# ESP32_mini.net
KiCad netlist of a schematic drawn in EAGLE
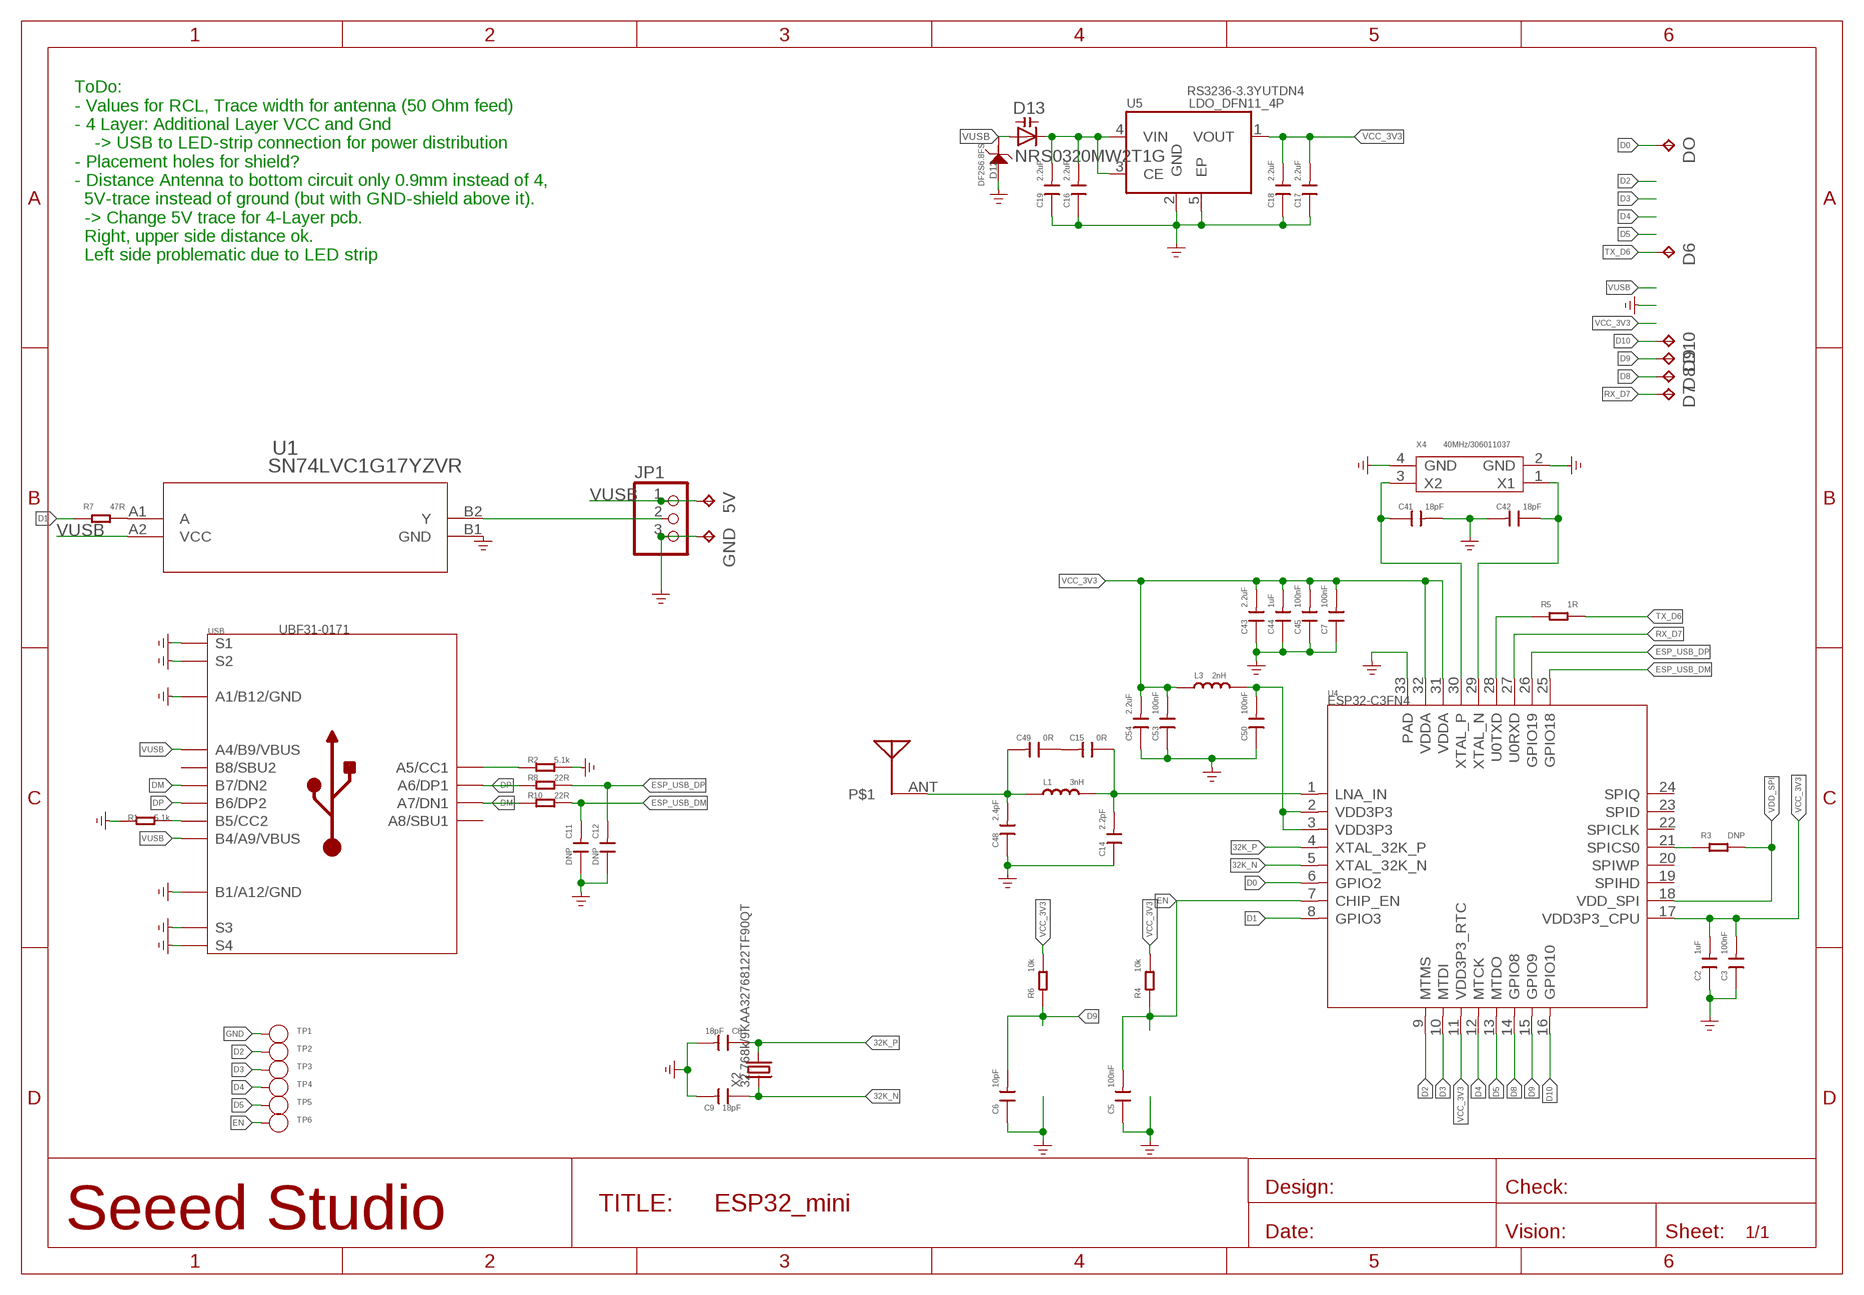
[diagram p0: schematic, sheet 1]

(export (version "E")
  (design (tool "Eeschema 10.0.6"))
  (components
    (comp (ref "5V")
      (value "TPTP07R")
      (footprint "eagle-import:TP07R")
      (libsource (lib "eagle-import") (part "TPTP07R"))
    )
    (comp (ref "C2")
      (value "1uF")
      (footprint "eagle-import:C0201")
      (libsource (lib "eagle-import") (part "CAP-0201"))
    )
    (comp (ref "C3")
      (value "100nF")
      (footprint "eagle-import:C0201")
      (libsource (lib "eagle-import") (part "CAP-0201"))
    )
    (comp (ref "C5")
      (value "100nF")
      (footprint "eagle-import:C0201")
      (libsource (lib "eagle-import") (part "CAP-0201"))
    )
    (comp (ref "C6")
      (value "10pF")
      (footprint "eagle-import:C0201")
      (libsource (lib "eagle-import") (part "CAP-0201"))
    )
    (comp (ref "C7")
      (value "100nF")
      (footprint "eagle-import:C0201")
      (libsource (lib "eagle-import") (part "CAP-0201"))
    )
    (comp (ref "C8")
      (value "18pF")
      (footprint "eagle-import:C0201")
      (libsource (lib "eagle-import") (part "CAP-0201"))
    )
    (comp (ref "C9")
      (value "18pF")
      (footprint "eagle-import:C0201")
      (libsource (lib "eagle-import") (part "CAP-0201"))
    )
    (comp (ref "C11")
      (value "DNP")
      (footprint "eagle-import:C0201")
      (libsource (lib "eagle-import") (part "CAP-0201"))
    )
    (comp (ref "C12")
      (value "DNP")
      (footprint "eagle-import:C0201")
      (libsource (lib "eagle-import") (part "CAP-0201"))
    )
    (comp (ref "C14")
      (value "2.2pF")
      (footprint "eagle-import:C0201")
      (libsource (lib "eagle-import") (part "CAP-0201"))
    )
    (comp (ref "C15")
      (value "0R")
      (footprint "eagle-import:C0201")
      (libsource (lib "eagle-import") (part "CAP-0201"))
    )
    (comp (ref "C16")
      (value "2.2uF")
      (footprint "eagle-import:C0201")
      (libsource (lib "eagle-import") (part "CAP-0201"))
    )
    (comp (ref "C17")
      (value "2.2uF")
      (footprint "eagle-import:C0201")
      (libsource (lib "eagle-import") (part "CAP-0201"))
    )
    (comp (ref "C18")
      (value "2.2uF")
      (footprint "eagle-import:C0201")
      (libsource (lib "eagle-import") (part "CAP-0201"))
    )
    (comp (ref "C19")
      (value "2.2uF")
      (footprint "eagle-import:C0201")
      (libsource (lib "eagle-import") (part "CAP-0201"))
    )
    (comp (ref "C41")
      (value "18pF")
      (footprint "eagle-import:C0201")
      (libsource (lib "eagle-import") (part "CAP-0201"))
    )
    (comp (ref "C42")
      (value "18pF")
      (footprint "eagle-import:C0201")
      (libsource (lib "eagle-import") (part "CAP-0201"))
    )
    (comp (ref "C43")
      (value "2.2uF")
      (footprint "eagle-import:C0201")
      (libsource (lib "eagle-import") (part "CAP-0201"))
    )
    (comp (ref "C44")
      (value "1uF")
      (footprint "eagle-import:C0201")
      (libsource (lib "eagle-import") (part "CAP-0201"))
    )
    (comp (ref "C45")
      (value "100nF")
      (footprint "eagle-import:C0201")
      (libsource (lib "eagle-import") (part "CAP-0201"))
    )
    (comp (ref "C48")
      (value "2.4pF")
      (footprint "eagle-import:C0201")
      (libsource (lib "eagle-import") (part "CAP-0201"))
    )
    (comp (ref "C49")
      (value "0R")
      (footprint "eagle-import:C0201")
      (libsource (lib "eagle-import") (part "CAP-0201"))
    )
    (comp (ref "C50")
      (value "100nF")
      (footprint "eagle-import:C0201")
      (libsource (lib "eagle-import") (part "CAP-0201"))
    )
    (comp (ref "C53")
      (value "100nF")
      (footprint "eagle-import:C0201")
      (libsource (lib "eagle-import") (part "CAP-0201"))
    )
    (comp (ref "C54")
      (value "2.2uF")
      (footprint "eagle-import:C0201")
      (libsource (lib "eagle-import") (part "CAP-0201"))
    )
    (comp (ref "D6")
      (value "TPTP07R")
      (footprint "eagle-import:TP07R")
      (libsource (lib "eagle-import") (part "TPTP07R"))
    )
    (comp (ref "D7")
      (value "TPTP07R")
      (footprint "eagle-import:TP07R")
      (libsource (lib "eagle-import") (part "TPTP07R"))
    )
    (comp (ref "D8")
      (value "TPTP07R")
      (footprint "eagle-import:TP07R")
      (libsource (lib "eagle-import") (part "TPTP07R"))
    )
    (comp (ref "D9")
      (value "TPTP07R")
      (footprint "eagle-import:TP07R")
      (libsource (lib "eagle-import") (part "TPTP07R"))
    )
    (comp (ref "D10")
      (value "TPTP07R")
      (footprint "eagle-import:TP07R")
      (libsource (lib "eagle-import") (part "TPTP07R"))
    )
    (comp (ref "D12")
      (value "DF2S6.8FS")
      (footprint "eagle-import:SOD-923")
      (libsource (lib "eagle-import") (part "D-ESD-2P'DF2S6.8FS'"))
    )
    (comp (ref "D13")
      (value "NRS0320MW2T1G")
      (footprint "eagle-import:SOD523")
      (libsource (lib "eagle-import") (part "DIODE_CAPACITANCE-SOD523"))
    )
    (comp (ref "DO")
      (value "TPTP09R")
      (footprint "eagle-import:TP09R")
      (libsource (lib "eagle-import") (part "TPTP09R"))
    )
    (comp (ref "GND")
      (value "TPTP07R")
      (footprint "eagle-import:TP07R")
      (libsource (lib "eagle-import") (part "TPTP07R"))
    )
    (comp (ref "JP1")
      (value "PINHD-1X3")
      (footprint "eagle-import:1X03")
      (libsource (lib "eagle-import") (part "PINHD-1X3"))
    )
    (comp (ref "L1")
      (value "3nH")
      (footprint "eagle-import:L0201")
      (libsource (lib "eagle-import") (part "INDUCTOR-0201"))
    )
    (comp (ref "L3")
      (value "2nH")
      (footprint "eagle-import:L0201")
      (libsource (lib "eagle-import") (part "INDUCTOR-0201"))
    )
    (comp (ref "R1")
      (value "5.1k")
      (footprint "eagle-import:R0201")
      (libsource (lib "eagle-import") (part "RES-0201"))
    )
    (comp (ref "R2")
      (value "5.1k")
      (footprint "eagle-import:R0201")
      (libsource (lib "eagle-import") (part "RES-0201"))
    )
    (comp (ref "R3")
      (value "DNP")
      (footprint "eagle-import:R0201")
      (libsource (lib "eagle-import") (part "RES-0201"))
    )
    (comp (ref "R4")
      (value "10k")
      (footprint "eagle-import:R0201")
      (libsource (lib "eagle-import") (part "RES-0201"))
    )
    (comp (ref "R5")
      (value "1R")
      (footprint "eagle-import:R0201")
      (libsource (lib "eagle-import") (part "RES-0201"))
    )
    (comp (ref "R6")
      (value "10k")
      (footprint "eagle-import:R0201")
      (libsource (lib "eagle-import") (part "RES-0201"))
    )
    (comp (ref "R7")
      (value "47R")
      (footprint "eagle-import:R0201")
      (libsource (lib "eagle-import") (part "RES-0201"))
    )
    (comp (ref "R8")
      (value "22R")
      (footprint "eagle-import:R0201")
      (libsource (lib "eagle-import") (part "RES-0201"))
    )
    (comp (ref "R10")
      (value "22R")
      (footprint "eagle-import:R0201")
      (libsource (lib "eagle-import") (part "RES-0201"))
    )
    (comp (ref "TP1")
      (value "DNP")
      (footprint "eagle-import:TP_3535")
      (libsource (lib "eagle-import") (part "TEST-POINT-35"))
    )
    (comp (ref "TP2")
      (value "DNP")
      (footprint "eagle-import:TP_3535")
      (libsource (lib "eagle-import") (part "TEST-POINT-35"))
    )
    (comp (ref "TP3")
      (value "DNP")
      (footprint "eagle-import:TP_3535")
      (libsource (lib "eagle-import") (part "TEST-POINT-35"))
    )
    (comp (ref "TP4")
      (value "DNP")
      (footprint "eagle-import:TP_3535")
      (libsource (lib "eagle-import") (part "TEST-POINT-35"))
    )
    (comp (ref "TP5")
      (value "DNP")
      (footprint "eagle-import:TP_3535")
      (libsource (lib "eagle-import") (part "TEST-POINT-35"))
    )
    (comp (ref "TP6")
      (value "DNP")
      (footprint "eagle-import:TP_3535")
      (libsource (lib "eagle-import") (part "TEST-POINT-35"))
    )
    (comp (ref "U$1")
      (value "KH5220-A36KH5220-A36")
      (footprint "eagle-import:KH5220-A36")
      (libsource (lib "eagle-import") (part "KH5220-A36KH5220-A36"))
    )
    (comp (ref "U1")
      (value "SN74LVC1G17YZVR")
      (footprint "eagle-import:YZV4")
      (fields (field (name "COPYRIGHT") "Copyright (C) 2024 Ultra Librarian. All rights reserved."))
      (libsource (lib "eagle-import") (part "SN74LVC1G17YZVR"))
    )
    (comp (ref "U4")
      (value "ESP32-C3FN4")
      (footprint "eagle-import:QFN32G-0.5-5X5MM")
      (libsource (lib "eagle-import") (part "MCU-ESP32-C3"))
    )
    (comp (ref "U5")
      (value "LDO_DFN11_4P")
      (footprint "eagle-import:LDO_DFN1_1_4P")
      (libsource (lib "eagle-import") (part "LDO_DFN11_4P"))
    )
    (comp (ref "USB")
      (value "UBF31-0171")
      (footprint "eagle-import:USB2.0-TYPE-C")
      (libsource (lib "eagle-import") (part "USB2.0-TYPE-C"))
    )
    (comp (ref "X2")
      (value "32.768k/9KAA32768122TF90QT")
      (footprint "eagle-import:X2-SMD-1.6X1.0X0.5MM")
      (libsource (lib "eagle-import") (part "CRYSTAL-2P-1610"))
    )
    (comp (ref "X4")
      (value "40MHz/306011037")
      (footprint "eagle-import:X4-SMD-2.0X1.6X0.5MM")
      (libsource (lib "eagle-import") (part "CRYSTAL-4P-2016"))
    )
  )
  (nets
    (net (code "1") (name "32K_N") (class "Default")
      (node (ref "C9") (pin "1") (pinfunction "1_1") (pintype "passive"))
      (node (ref "U4") (pin "5") (pinfunction "XTAL_32K_N_5") (pintype "bidirectional"))
      (node (ref "X2") (pin "1") (pinfunction "1_1") (pintype "passive"))
    )
    (net (code "2") (name "32K_P") (class "Default")
      (node (ref "C8") (pin "1") (pinfunction "1_1") (pintype "passive"))
      (node (ref "U4") (pin "4") (pinfunction "XTAL_32K_P_4") (pintype "bidirectional"))
      (node (ref "X2") (pin "2") (pinfunction "2_2") (pintype "passive"))
    )
    (net (code "3") (name "D0") (class "Default")
      (node (ref "DO") (pin "TP") (pinfunction "TP_TP") (pintype "input"))
      (node (ref "U4") (pin "6") (pinfunction "GPIO2_6") (pintype "bidirectional"))
    )
    (net (code "4") (name "D1") (class "Default")
      (node (ref "R7") (pin "2") (pinfunction "2_2") (pintype "passive"))
      (node (ref "U4") (pin "8") (pinfunction "GPIO3_8") (pintype "bidirectional"))
    )
    (net (code "5") (name "D2") (class "Default")
      (node (ref "TP2") (pin "T") (pinfunction "T_T") (pintype "bidirectional"))
      (node (ref "U4") (pin "9") (pinfunction "MTMS_9") (pintype "bidirectional"))
    )
    (net (code "6") (name "D3") (class "Default")
      (node (ref "TP3") (pin "T") (pinfunction "T_T") (pintype "bidirectional"))
      (node (ref "U4") (pin "10") (pinfunction "MTDI_10") (pintype "bidirectional"))
    )
    (net (code "7") (name "D4") (class "Default")
      (node (ref "TP4") (pin "T") (pinfunction "T_T") (pintype "bidirectional"))
      (node (ref "U4") (pin "12") (pinfunction "MTCK_12") (pintype "bidirectional"))
    )
    (net (code "8") (name "D5") (class "Default")
      (node (ref "TP5") (pin "T") (pinfunction "T_T") (pintype "bidirectional"))
      (node (ref "U4") (pin "13") (pinfunction "MTDO_13") (pintype "bidirectional"))
    )
    (net (code "9") (name "D8") (class "Default")
      (node (ref "D8") (pin "TP") (pinfunction "TP_TP") (pintype "input"))
      (node (ref "U4") (pin "14") (pinfunction "GPIO8_14") (pintype "bidirectional"))
    )
    (net (code "10") (name "D9") (class "Default")
      (node (ref "C6") (pin "2") (pinfunction "2_2") (pintype "passive"))
      (node (ref "D9") (pin "TP") (pinfunction "TP_TP") (pintype "input"))
      (node (ref "R6") (pin "1") (pinfunction "1_1") (pintype "passive"))
      (node (ref "U4") (pin "15") (pinfunction "GPIO9_15") (pintype "bidirectional"))
    )
    (net (code "11") (name "D10") (class "Default")
      (node (ref "D10") (pin "TP") (pinfunction "TP_TP") (pintype "input"))
      (node (ref "U4") (pin "16") (pinfunction "GPIO10_16") (pintype "bidirectional"))
    )
    (net (code "12") (name "DM") (class "Default")
      (node (ref "R10") (pin "1") (pinfunction "1_1") (pintype "passive"))
      (node (ref "USB") (pin "A7") (pinfunction "A7/DN1_A7") (pintype "bidirectional"))
      (node (ref "USB") (pin "B7") (pinfunction "B7/DN2_B7") (pintype "bidirectional"))
    )
    (net (code "13") (name "DP") (class "Default")
      (node (ref "R8") (pin "1") (pinfunction "1_1") (pintype "passive"))
      (node (ref "USB") (pin "A6") (pinfunction "A6/DP1_A6") (pintype "bidirectional"))
      (node (ref "USB") (pin "B6") (pinfunction "B6/DP2_B6") (pintype "bidirectional"))
    )
    (net (code "14") (name "EN") (class "Default")
      (node (ref "C5") (pin "2") (pinfunction "2_2") (pintype "passive"))
      (node (ref "R4") (pin "1") (pinfunction "1_1") (pintype "passive"))
      (node (ref "TP6") (pin "T") (pinfunction "T_T") (pintype "bidirectional"))
      (node (ref "U4") (pin "7") (pinfunction "CHIP_EN_7") (pintype "bidirectional"))
    )
    (net (code "15") (name "ESP_USB_DM") (class "Default")
      (node (ref "C11") (pin "2") (pinfunction "2_2") (pintype "passive"))
      (node (ref "R10") (pin "2") (pinfunction "2_2") (pintype "passive"))
      (node (ref "U4") (pin "25") (pinfunction "GPIO18_25") (pintype "bidirectional"))
    )
    (net (code "16") (name "ESP_USB_DP") (class "Default")
      (node (ref "C12") (pin "2") (pinfunction "2_2") (pintype "passive"))
      (node (ref "R8") (pin "2") (pinfunction "2_2") (pintype "passive"))
      (node (ref "U4") (pin "26") (pinfunction "GPIO19_26") (pintype "bidirectional"))
    )
    (net (code "17") (name "GND") (class "Default")
      (node (ref "C11") (pin "1") (pinfunction "1_1") (pintype "passive"))
      (node (ref "C12") (pin "1") (pinfunction "1_1") (pintype "passive"))
      (node (ref "C14") (pin "1") (pinfunction "1_1") (pintype "passive"))
      (node (ref "C16") (pin "1") (pinfunction "1_1") (pintype "passive"))
      (node (ref "C17") (pin "1") (pinfunction "1_1") (pintype "passive"))
      (node (ref "C18") (pin "1") (pinfunction "1_1") (pintype "passive"))
      (node (ref "C19") (pin "1") (pinfunction "1_1") (pintype "passive"))
      (node (ref "C2") (pin "1") (pinfunction "1_1") (pintype "passive"))
      (node (ref "C3") (pin "1") (pinfunction "1_1") (pintype "passive"))
      (node (ref "C41") (pin "2") (pinfunction "2_2") (pintype "passive"))
      (node (ref "C42") (pin "2") (pinfunction "2_2") (pintype "passive"))
      (node (ref "C43") (pin "1") (pinfunction "1_1") (pintype "passive"))
      (node (ref "C44") (pin "1") (pinfunction "1_1") (pintype "passive"))
      (node (ref "C45") (pin "1") (pinfunction "1_1") (pintype "passive"))
      (node (ref "C48") (pin "1") (pinfunction "1_1") (pintype "passive"))
      (node (ref "C5") (pin "1") (pinfunction "1_1") (pintype "passive"))
      (node (ref "C50") (pin "1") (pinfunction "1_1") (pintype "passive"))
      (node (ref "C53") (pin "1") (pinfunction "1_1") (pintype "passive"))
      (node (ref "C54") (pin "1") (pinfunction "1_1") (pintype "passive"))
      (node (ref "C6") (pin "1") (pinfunction "1_1") (pintype "passive"))
      (node (ref "C7") (pin "1") (pinfunction "1_1") (pintype "passive"))
      (node (ref "C8") (pin "2") (pinfunction "2_2") (pintype "passive"))
      (node (ref "C9") (pin "2") (pinfunction "2_2") (pintype "passive"))
      (node (ref "D12") (pin "2") (pinfunction "1_2") (pintype "bidirectional"))
      (node (ref "GND") (pin "TP") (pinfunction "TP_TP") (pintype "input"))
      (node (ref "JP1") (pin "3") (pinfunction "3_3") (pintype "passive"))
      (node (ref "R1") (pin "1") (pinfunction "1_1") (pintype "passive"))
      (node (ref "R2") (pin "2") (pinfunction "2_2") (pintype "passive"))
      (node (ref "TP1") (pin "T") (pinfunction "T_T") (pintype "bidirectional"))
      (node (ref "U1") (pin "B1") (pinfunction "GND_B1") (pintype "power_in"))
      (node (ref "U4") (pin "33") (pinfunction "PAD_33") (pintype "bidirectional"))
      (node (ref "U5") (pin "2") (pinfunction "GND_2") (pintype "bidirectional"))
      (node (ref "U5") (pin "5") (pinfunction "EP_5") (pintype "bidirectional"))
      (node (ref "USB") (pin "A1_B12") (pinfunction "A1/B12/GND_A1_B12") (pintype "bidirectional"))
      (node (ref "USB") (pin "B1_A12") (pinfunction "B1/A12/GND_B1_A12") (pintype "bidirectional"))
      (node (ref "USB") (pin "S1") (pinfunction "S1_S1") (pintype "bidirectional"))
      (node (ref "USB") (pin "S2") (pinfunction "S2_S2") (pintype "bidirectional"))
      (node (ref "USB") (pin "S3") (pinfunction "S3_S3") (pintype "bidirectional"))
      (node (ref "USB") (pin "S4") (pinfunction "S4_S4") (pintype "bidirectional"))
      (node (ref "USB") (pin "S5") (pinfunction "S1_S5") (pintype "bidirectional"))
      (node (ref "USB") (pin "S6") (pinfunction "S2_S6") (pintype "bidirectional"))
      (node (ref "X4") (pin "2") (pinfunction "GND_2") (pintype "bidirectional"))
      (node (ref "X4") (pin "4") (pinfunction "GND_4") (pintype "bidirectional"))
    )
    (net (code "18") (name "Net-(C15-Pad2)") (class "Default")
      (node (ref "C15") (pin "2") (pinfunction "2_2") (pintype "passive"))
      (node (ref "C49") (pin "1") (pinfunction "1_1") (pintype "passive"))
    )
    (net (code "19") (name "Net-(C50-Pad2)") (class "Default")
      (node (ref "C50") (pin "2") (pinfunction "2_2") (pintype "passive"))
      (node (ref "L3") (pin "2") (pinfunction "2_2") (pintype "passive"))
      (node (ref "U4") (pin "2") (pinfunction "VDD3P3_2") (pintype "bidirectional"))
      (node (ref "U4") (pin "3") (pinfunction "VDD3P3_3") (pintype "bidirectional"))
    )
    (net (code "20") (name "Net-(U$1-P$1)") (class "Default")
      (node (ref "C48") (pin "2") (pinfunction "2_2") (pintype "passive"))
      (node (ref "C49") (pin "2") (pinfunction "2_2") (pintype "passive"))
      (node (ref "L1") (pin "1") (pinfunction "1_1") (pintype "passive"))
      (node (ref "U$1") (pin "ANT") (pinfunction "P$1_ANT") (pintype "bidirectional"))
    )
    (net (code "21") (name "Net-(U1-A)") (class "Default")
      (node (ref "R7") (pin "1") (pinfunction "1_1") (pintype "passive"))
      (node (ref "U1") (pin "A1") (pinfunction "A_A1") (pintype "input"))
    )
    (net (code "22") (name "Net-(U1-Y)") (class "Default")
      (node (ref "JP1") (pin "2") (pinfunction "2_2") (pintype "passive"))
      (node (ref "U1") (pin "B2") (pinfunction "Y_B2") (pintype "output"))
    )
    (net (code "23") (name "Net-(U4-LNA_IN)") (class "Default")
      (node (ref "C14") (pin "2") (pinfunction "2_2") (pintype "passive"))
      (node (ref "C15") (pin "1") (pinfunction "1_1") (pintype "passive"))
      (node (ref "L1") (pin "2") (pinfunction "2_2") (pintype "passive"))
      (node (ref "U4") (pin "1") (pinfunction "LNA_IN_1") (pintype "bidirectional"))
    )
    (net (code "24") (name "Net-(U4-SPICS0)") (class "Default")
      (node (ref "R3") (pin "1") (pinfunction "1_1") (pintype "passive"))
      (node (ref "U4") (pin "21") (pinfunction "SPICS0_21") (pintype "bidirectional"))
    )
    (net (code "25") (name "Net-(U4-U0TXD)") (class "Default")
      (node (ref "R5") (pin "2") (pinfunction "2_2") (pintype "passive"))
      (node (ref "U4") (pin "28") (pinfunction "U0TXD_28") (pintype "bidirectional"))
    )
    (net (code "26") (name "Net-(U4-XTAL_N)") (class "Default")
      (node (ref "C42") (pin "1") (pinfunction "1_1") (pintype "passive"))
      (node (ref "U4") (pin "29") (pinfunction "XTAL_N_29") (pintype "bidirectional"))
      (node (ref "X4") (pin "1") (pinfunction "X1_1") (pintype "bidirectional"))
    )
    (net (code "27") (name "Net-(U4-XTAL_P)") (class "Default")
      (node (ref "C41") (pin "1") (pinfunction "1_1") (pintype "passive"))
      (node (ref "U4") (pin "30") (pinfunction "XTAL_P_30") (pintype "bidirectional"))
      (node (ref "X4") (pin "3") (pinfunction "X2_3") (pintype "bidirectional"))
    )
    (net (code "28") (name "Net-(U5-CE)") (class "Default")
      (node (ref "C16") (pin "2") (pinfunction "2_2") (pintype "passive"))
      (node (ref "C19") (pin "2") (pinfunction "2_2") (pintype "passive"))
      (node (ref "D13") (pin "C") (pinfunction "C_C") (pintype "passive"))
      (node (ref "U5") (pin "3") (pinfunction "CE_3") (pintype "bidirectional"))
      (node (ref "U5") (pin "4") (pinfunction "VIN_4") (pintype "bidirectional"))
    )
    (net (code "29") (name "Net-(USB-A5{slash}CC1)") (class "Default")
      (node (ref "R2") (pin "1") (pinfunction "1_1") (pintype "passive"))
      (node (ref "USB") (pin "A5") (pinfunction "A5/CC1_A5") (pintype "bidirectional"))
    )
    (net (code "30") (name "Net-(USB-B5{slash}CC2)") (class "Default")
      (node (ref "R1") (pin "2") (pinfunction "2_2") (pintype "passive"))
      (node (ref "USB") (pin "B5") (pinfunction "B5/CC2_B5") (pintype "bidirectional"))
    )
    (net (code "31") (name "RX_D7") (class "Default")
      (node (ref "D7") (pin "TP") (pinfunction "TP_TP") (pintype "input"))
      (node (ref "U4") (pin "27") (pinfunction "U0RXD_27") (pintype "bidirectional"))
    )
    (net (code "32") (name "TX_D6") (class "Default")
      (node (ref "D6") (pin "TP") (pinfunction "TP_TP") (pintype "input"))
      (node (ref "R5") (pin "1") (pinfunction "1_1") (pintype "passive"))
    )
    (net (code "33") (name "VCC_3V3") (class "Default")
      (node (ref "C17") (pin "2") (pinfunction "2_2") (pintype "passive"))
      (node (ref "C18") (pin "2") (pinfunction "2_2") (pintype "passive"))
      (node (ref "C2") (pin "2") (pinfunction "2_2") (pintype "passive"))
      (node (ref "C3") (pin "2") (pinfunction "2_2") (pintype "passive"))
      (node (ref "C43") (pin "2") (pinfunction "2_2") (pintype "passive"))
      (node (ref "C44") (pin "2") (pinfunction "2_2") (pintype "passive"))
      (node (ref "C45") (pin "2") (pinfunction "2_2") (pintype "passive"))
      (node (ref "C53") (pin "2") (pinfunction "2_2") (pintype "passive"))
      (node (ref "C54") (pin "2") (pinfunction "2_2") (pintype "passive"))
      (node (ref "C7") (pin "2") (pinfunction "2_2") (pintype "passive"))
      (node (ref "L3") (pin "1") (pinfunction "1_1") (pintype "passive"))
      (node (ref "R4") (pin "2") (pinfunction "2_2") (pintype "passive"))
      (node (ref "R6") (pin "2") (pinfunction "2_2") (pintype "passive"))
      (node (ref "U4") (pin "11") (pinfunction "VDD3P3_RTC_11") (pintype "bidirectional"))
      (node (ref "U4") (pin "17") (pinfunction "VDD3P3_CPU_17") (pintype "bidirectional"))
      (node (ref "U4") (pin "31") (pinfunction "VDDA_31") (pintype "bidirectional"))
      (node (ref "U4") (pin "32") (pinfunction "VDDA_32") (pintype "bidirectional"))
      (node (ref "U5") (pin "1") (pinfunction "VOUT_1") (pintype "bidirectional"))
    )
    (net (code "34") (name "VDD_SPI") (class "Default")
      (node (ref "R3") (pin "2") (pinfunction "2_2") (pintype "passive"))
      (node (ref "U4") (pin "18") (pinfunction "VDD_SPI_18") (pintype "bidirectional"))
    )
    (net (code "35") (name "VUSB") (class "Default")
      (node (ref "5V") (pin "TP") (pinfunction "TP_TP") (pintype "input"))
      (node (ref "D12") (pin "1") (pinfunction "2_1") (pintype "bidirectional"))
      (node (ref "D13") (pin "A") (pinfunction "A_A") (pintype "passive"))
      (node (ref "JP1") (pin "1") (pinfunction "1_1") (pintype "passive"))
      (node (ref "U1") (pin "A2") (pinfunction "VCC_A2") (pintype "power_in"))
      (node (ref "USB") (pin "A4_B9") (pinfunction "A4/B9/VBUS_A4_B9") (pintype "bidirectional"))
      (node (ref "USB") (pin "B4_A9") (pinfunction "B4/A9/VBUS_B4_A9") (pintype "bidirectional"))
    )
    (net (code "36") (name "unconnected-(U4-SPICLK-Pad22)") (class "Default")
      (node (ref "U4") (pin "22") (pinfunction "SPICLK_22") (pintype "bidirectional"))
    )
    (net (code "37") (name "unconnected-(U4-SPID-Pad23)") (class "Default")
      (node (ref "U4") (pin "23") (pinfunction "SPID_23") (pintype "bidirectional"))
    )
    (net (code "38") (name "unconnected-(U4-SPIHD-Pad19)") (class "Default")
      (node (ref "U4") (pin "19") (pinfunction "SPIHD_19") (pintype "bidirectional"))
    )
    (net (code "39") (name "unconnected-(U4-SPIQ-Pad24)") (class "Default")
      (node (ref "U4") (pin "24") (pinfunction "SPIQ_24") (pintype "bidirectional"))
    )
    (net (code "40") (name "unconnected-(U4-SPIWP-Pad20)") (class "Default")
      (node (ref "U4") (pin "20") (pinfunction "SPIWP_20") (pintype "bidirectional"))
    )
    (net (code "41") (name "unconnected-(USB-A8{slash}SBU1-PadA8)") (class "Default")
      (node (ref "USB") (pin "A8") (pinfunction "A8/SBU1_A8") (pintype "bidirectional"))
    )
    (net (code "42") (name "unconnected-(USB-B8{slash}SBU2-PadB8)") (class "Default")
      (node (ref "USB") (pin "B8") (pinfunction "B8/SBU2_B8") (pintype "bidirectional"))
    )
  )
)
